# IMU.net
KiCad netlist of a schematic drawn in EAGLE
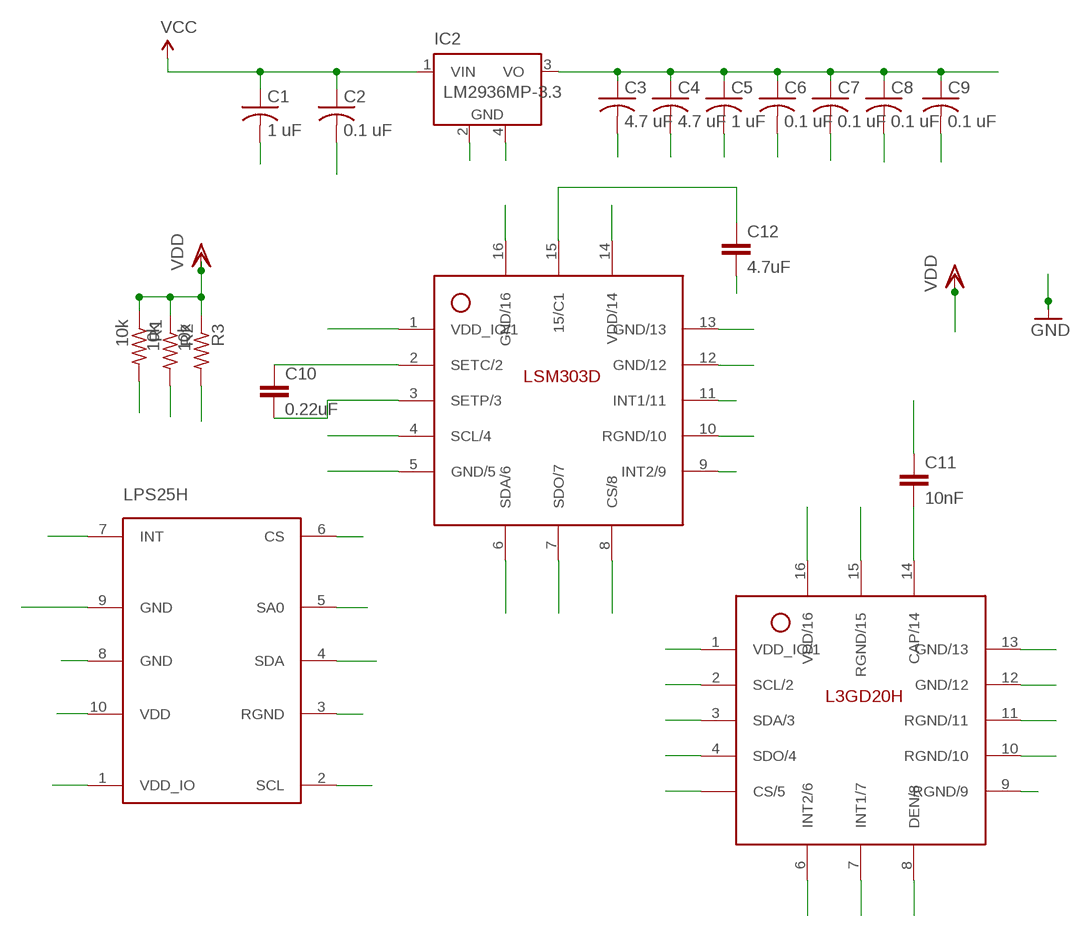
[diagram p0: schematic, sheet 1]

(export (version "E")
  (design (tool "Eeschema 10.0.6"))
  (components
    (comp (ref "C1")
      (value "1 uF")
      (footprint "eagle-import:C0805")
      (libsource (lib "eagle-import") (part "C-USC0805"))
    )
    (comp (ref "C2")
      (value "0.1 uF")
      (footprint "eagle-import:C0805")
      (libsource (lib "eagle-import") (part "C-USC0805"))
    )
    (comp (ref "C3")
      (value "4.7 uF")
      (footprint "eagle-import:C0805")
      (libsource (lib "eagle-import") (part "C-USC0805"))
    )
    (comp (ref "C4")
      (value "4.7 uF")
      (footprint "eagle-import:C0805")
      (libsource (lib "eagle-import") (part "C-USC0805"))
    )
    (comp (ref "C5")
      (value "1 uF")
      (footprint "eagle-import:C0805")
      (libsource (lib "eagle-import") (part "C-USC0805"))
    )
    (comp (ref "C6")
      (value "0.1 uF")
      (footprint "eagle-import:C0805")
      (libsource (lib "eagle-import") (part "C-USC0805"))
    )
    (comp (ref "C7")
      (value "0.1 uF")
      (footprint "eagle-import:C0805")
      (libsource (lib "eagle-import") (part "C-USC0805"))
    )
    (comp (ref "C8")
      (value "0.1 uF")
      (footprint "eagle-import:C0805")
      (libsource (lib "eagle-import") (part "C-USC0805"))
    )
    (comp (ref "C9")
      (value "0.1 uF")
      (footprint "eagle-import:C0805")
      (libsource (lib "eagle-import") (part "C-USC0805"))
    )
    (comp (ref "C10")
      (value "0.22uF")
      (footprint "eagle-import:0603-CAP")
      (libsource (lib "eagle-import") (part "0.22UF50V-20%,+80%(0603)"))
    )
    (comp (ref "C11")
      (value "10nF")
      (footprint "eagle-import:0603-CAP")
      (libsource (lib "eagle-import") (part "10NF/10000PF-50V-10%(0603)"))
    )
    (comp (ref "C12")
      (value "4.7uF")
      (footprint "eagle-import:0603-CAP")
      (libsource (lib "eagle-import") (part "4.7UF-6.3V-10%(0603)0603"))
    )
    (comp (ref "IC2")
      (value "LM2936MP-3.3")
      (footprint "eagle-import:SOT223")
      (fields (field (name "MF") "NATIONAL SEMICONDUCTOR") (field (name "MPN") "LM2936MP-3.3/NOPB"))
      (libsource (lib "eagle-import") (part "LM2936MP?-3.3"))
    )
    (comp (ref "LPS25H")
      (value "LPS25H")
      (footprint "eagle-import:LPS25H")
      (libsource (lib "eagle-import") (part "LPS25H"))
    )
    (comp (ref "R1")
      (value "10k")
      (footprint "eagle-import:R0805")
      (libsource (lib "eagle-import") (part "R-US_R0805"))
    )
    (comp (ref "R2")
      (value "10k")
      (footprint "eagle-import:R0805")
      (libsource (lib "eagle-import") (part "R-US_R0805"))
    )
    (comp (ref "R3")
      (value "10k")
      (footprint "eagle-import:R0805")
      (libsource (lib "eagle-import") (part "R-US_R0805"))
    )
    (comp (ref "U$1")
      (value "L3GD20H")
      (footprint "eagle-import:LGA-16")
      (libsource (lib "eagle-import") (part "L3GD20H"))
    )
    (comp (ref "U$2")
      (value "LSM303D")
      (footprint "eagle-import:LGA-16")
      (libsource (lib "eagle-import") (part "LSM303D"))
    )
  )
  (nets
    (net (code "1") (name "/SCL") (class "Default")
      (node (ref "LPS25H") (pin "2") (pinfunction "SCL_2") (pintype "bidirectional"))
      (node (ref "R2") (pin "2") (pinfunction "2_2") (pintype "passive"))
      (node (ref "U$1") (pin "2") (pinfunction "SCL/2_2") (pintype "bidirectional"))
      (node (ref "U$2") (pin "4") (pinfunction "SCL/4_4") (pintype "bidirectional"))
    )
    (net (code "2") (name "/SDA") (class "Default")
      (node (ref "LPS25H") (pin "4") (pinfunction "SDA_4") (pintype "bidirectional"))
      (node (ref "R1") (pin "2") (pinfunction "2_2") (pintype "passive"))
      (node (ref "U$1") (pin "3") (pinfunction "SDA/3_3") (pintype "bidirectional"))
      (node (ref "U$2") (pin "6") (pinfunction "SDA/6_6") (pintype "bidirectional"))
    )
    (net (code "3") (name "/SDO") (class "Default")
      (node (ref "LPS25H") (pin "5") (pinfunction "SA0_5") (pintype "bidirectional"))
      (node (ref "R3") (pin "2") (pinfunction "2_2") (pintype "passive"))
      (node (ref "U$1") (pin "4") (pinfunction "SDO/4_4") (pintype "bidirectional"))
      (node (ref "U$2") (pin "7") (pinfunction "SDO/7_7") (pintype "bidirectional"))
    )
    (net (code "4") (name "GND") (class "Default")
      (node (ref "C1") (pin "2") (pinfunction "2_2") (pintype "passive"))
      (node (ref "C11") (pin "1") (pinfunction "1_1") (pintype "passive"))
      (node (ref "C12") (pin "2") (pinfunction "2_2") (pintype "passive"))
      (node (ref "C2") (pin "2") (pinfunction "2_2") (pintype "passive"))
      (node (ref "C3") (pin "2") (pinfunction "2_2") (pintype "passive"))
      (node (ref "C4") (pin "2") (pinfunction "2_2") (pintype "passive"))
      (node (ref "C5") (pin "2") (pinfunction "2_2") (pintype "passive"))
      (node (ref "C6") (pin "2") (pinfunction "2_2") (pintype "passive"))
      (node (ref "C7") (pin "2") (pinfunction "2_2") (pintype "passive"))
      (node (ref "C8") (pin "2") (pinfunction "2_2") (pintype "passive"))
      (node (ref "C9") (pin "2") (pinfunction "2_2") (pintype "passive"))
      (node (ref "IC2") (pin "2") (pinfunction "GND_2") (pintype "passive"))
      (node (ref "IC2") (pin "4") (pinfunction "GND_4") (pintype "passive"))
      (node (ref "LPS25H") (pin "8") (pinfunction "GND_8") (pintype "power_in"))
      (node (ref "LPS25H") (pin "9") (pinfunction "GND_9") (pintype "power_in"))
      (node (ref "U$1") (pin "10") (pinfunction "RGND/10_10") (pintype "bidirectional"))
      (node (ref "U$1") (pin "11") (pinfunction "RGND/11_11") (pintype "bidirectional"))
      (node (ref "U$1") (pin "12") (pinfunction "GND/12_12") (pintype "bidirectional"))
      (node (ref "U$1") (pin "13") (pinfunction "GND/13_13") (pintype "bidirectional"))
      (node (ref "U$1") (pin "16") (pinfunction "VDD/16_16") (pintype "bidirectional"))
      (node (ref "U$1") (pin "8") (pinfunction "DEN/8_8") (pintype "bidirectional"))
      (node (ref "U$1") (pin "9") (pinfunction "RGND/9_9") (pintype "bidirectional"))
      (node (ref "U$2") (pin "10") (pinfunction "RGND/10_10") (pintype "bidirectional"))
      (node (ref "U$2") (pin "12") (pinfunction "GND/12_12") (pintype "bidirectional"))
      (node (ref "U$2") (pin "13") (pinfunction "GND/13_13") (pintype "bidirectional"))
      (node (ref "U$2") (pin "16") (pinfunction "GND/16_16") (pintype "bidirectional"))
      (node (ref "U$2") (pin "5") (pinfunction "GND/5_5") (pintype "bidirectional"))
    )
    (net (code "5") (name "Net-(U$1-CAP{slash}14)") (class "Default")
      (node (ref "C11") (pin "2") (pinfunction "2_2") (pintype "passive"))
      (node (ref "U$1") (pin "14") (pinfunction "CAP/14_14") (pintype "bidirectional"))
    )
    (net (code "6") (name "Net-(U$2-15{slash}C1)") (class "Default")
      (node (ref "C12") (pin "1") (pinfunction "1_1") (pintype "passive"))
      (node (ref "U$2") (pin "15") (pinfunction "15/C1_15") (pintype "bidirectional"))
    )
    (net (code "7") (name "Net-(U$2-SETC{slash}2)") (class "Default")
      (node (ref "C10") (pin "1") (pinfunction "1_1") (pintype "passive"))
      (node (ref "U$2") (pin "2") (pinfunction "SETC/2_2") (pintype "bidirectional"))
    )
    (net (code "8") (name "Net-(U$2-SETP{slash}3)") (class "Default")
      (node (ref "C10") (pin "2") (pinfunction "2_2") (pintype "passive"))
      (node (ref "U$2") (pin "3") (pinfunction "SETP/3_3") (pintype "bidirectional"))
    )
    (net (code "9") (name "VCC") (class "Default")
      (node (ref "C1") (pin "1") (pinfunction "1_1") (pintype "passive"))
      (node (ref "C2") (pin "1") (pinfunction "1_1") (pintype "passive"))
      (node (ref "IC2") (pin "1") (pinfunction "VIN_1") (pintype "input"))
    )
    (net (code "10") (name "VDD") (class "Default")
      (node (ref "C3") (pin "1") (pinfunction "1_1") (pintype "passive"))
      (node (ref "C4") (pin "1") (pinfunction "1_1") (pintype "passive"))
      (node (ref "C5") (pin "1") (pinfunction "1_1") (pintype "passive"))
      (node (ref "C6") (pin "1") (pinfunction "1_1") (pintype "passive"))
      (node (ref "C7") (pin "1") (pinfunction "1_1") (pintype "passive"))
      (node (ref "C8") (pin "1") (pinfunction "1_1") (pintype "passive"))
      (node (ref "C9") (pin "1") (pinfunction "1_1") (pintype "passive"))
      (node (ref "IC2") (pin "3") (pinfunction "VO_3") (pintype "passive"))
      (node (ref "LPS25H") (pin "1") (pinfunction "VDD_IO_1") (pintype "power_in"))
      (node (ref "LPS25H") (pin "10") (pinfunction "VDD_10") (pintype "power_in"))
      (node (ref "LPS25H") (pin "6") (pinfunction "CS_6") (pintype "bidirectional"))
      (node (ref "R1") (pin "1") (pinfunction "1_1") (pintype "passive"))
      (node (ref "R2") (pin "1") (pinfunction "1_1") (pintype "passive"))
      (node (ref "R3") (pin "1") (pinfunction "1_1") (pintype "passive"))
      (node (ref "U$1") (pin "1") (pinfunction "VDD_IO/1_1") (pintype "bidirectional"))
      (node (ref "U$1") (pin "15") (pinfunction "RGND/15_15") (pintype "bidirectional"))
      (node (ref "U$1") (pin "5") (pinfunction "CS/5_5") (pintype "bidirectional"))
      (node (ref "U$2") (pin "1") (pinfunction "VDD_IO/1_1") (pintype "bidirectional"))
      (node (ref "U$2") (pin "14") (pinfunction "VDD/14_14") (pintype "bidirectional"))
      (node (ref "U$2") (pin "8") (pinfunction "CS/8_8") (pintype "bidirectional"))
    )
    (net (code "11") (name "unconnected-(LPS25H-INT-Pad7)") (class "Default")
      (node (ref "LPS25H") (pin "7") (pinfunction "INT_7") (pintype "bidirectional"))
    )
    (net (code "12") (name "unconnected-(LPS25H-RGND-Pad3)") (class "Default")
      (node (ref "LPS25H") (pin "3") (pinfunction "RGND_3") (pintype "bidirectional"))
    )
    (net (code "13") (name "unconnected-(U$1-INT1{slash}7-Pad7)") (class "Default")
      (node (ref "U$1") (pin "7") (pinfunction "INT1/7_7") (pintype "bidirectional"))
    )
    (net (code "14") (name "unconnected-(U$1-INT2{slash}6-Pad6)") (class "Default")
      (node (ref "U$1") (pin "6") (pinfunction "INT2/6_6") (pintype "bidirectional"))
    )
    (net (code "15") (name "unconnected-(U$2-INT1{slash}11-Pad11)") (class "Default")
      (node (ref "U$2") (pin "11") (pinfunction "INT1/11_11") (pintype "bidirectional"))
    )
    (net (code "16") (name "unconnected-(U$2-INT2{slash}9-Pad9)") (class "Default")
      (node (ref "U$2") (pin "9") (pinfunction "INT2/9_9") (pintype "bidirectional"))
    )
  )
)
